# BlueTooth.net
KiCad netlist of a schematic drawn in Altium Designer
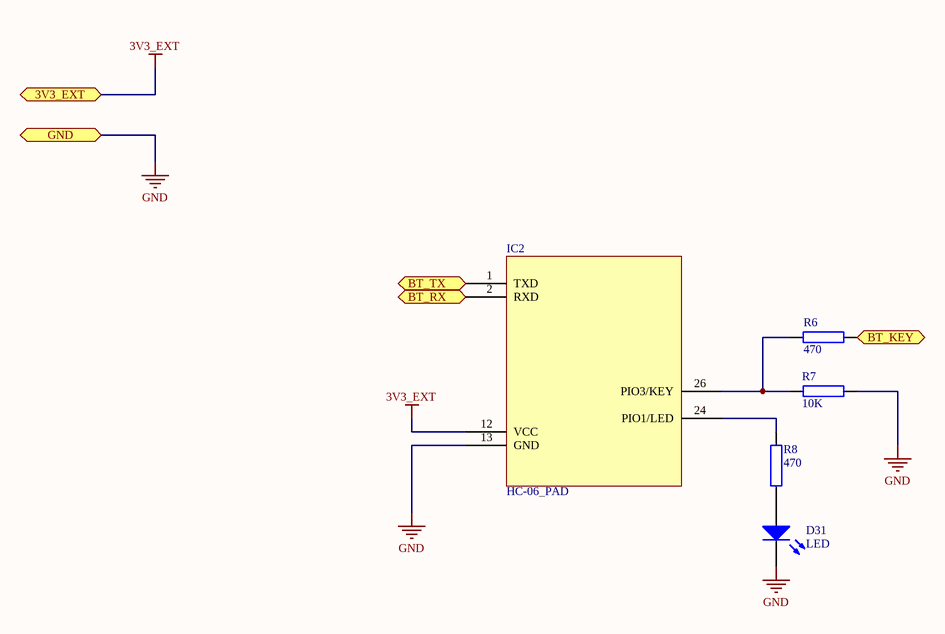
[diagram p0: BlueTooth.SchDoc]

(export (version "E")
  (design (tool "Eeschema 10.0.6"))
  (components
    (comp (ref "D31")
      (value "LED")
      (footprint "LED_0603")
      (description "Typical INFRARED GaAs LED")
      (fields (field (name "PUBLISHER") "Altium Limited"))
      (libsource (lib "Quadcopter") (part "LED"))
    )
    (comp (ref "IC2")
      (value "HC-06_PAD")
      (footprint "HC-0X_PAD")
      (libsource (lib "Quadcopter") (part "HC-06_PAD"))
    )
    (comp (ref "R6")
      (value "470")
      (footprint "R0603")
      (description "Resistor")
      (fields (field (name "PUBLISHER") "Altium Limited"))
      (libsource (lib "Quadcopter") (part "Res3"))
    )
    (comp (ref "R7")
      (value "10K")
      (footprint "R0603")
      (description "Resistor")
      (fields (field (name "PUBLISHER") "Altium Limited"))
      (libsource (lib "Quadcopter") (part "Res3"))
    )
    (comp (ref "R8")
      (value "470")
      (footprint "R0603")
      (description "Resistor")
      (fields (field (name "PUBLISHER") "Altium Limited"))
      (libsource (lib "Quadcopter") (part "Res3"))
    )
  )
  (nets
    (net (code "1") (name "/BT_KEY") (class "Default")
      (node (ref "R6") (pin "2") (pinfunction "2_2") (pintype "passive"))
    )
    (net (code "2") (name "/BT_RX") (class "Default")
      (node (ref "IC2") (pin "2") (pinfunction "RXD_2") (pintype "passive"))
    )
    (net (code "3") (name "/BT_TX") (class "Default")
      (node (ref "IC2") (pin "1") (pinfunction "TXD_1") (pintype "passive"))
    )
    (net (code "4") (name "3V3_EXT") (class "Default")
      (node (ref "IC2") (pin "12") (pinfunction "VCC_12") (pintype "passive"))
    )
    (net (code "5") (name "GND") (class "Default")
      (node (ref "D31") (pin "2") (pinfunction "K_2") (pintype "passive"))
      (node (ref "IC2") (pin "13") (pinfunction "GND_13") (pintype "passive"))
      (node (ref "R7") (pin "2") (pinfunction "2_2") (pintype "passive"))
    )
    (net (code "6") (name "Net-(D31-A)") (class "Default")
      (node (ref "D31") (pin "1") (pinfunction "A_1") (pintype "passive"))
      (node (ref "R8") (pin "1") (pinfunction "1_1") (pintype "passive"))
    )
    (net (code "7") (name "Net-(IC2-PIO1{slash}LED)") (class "Default")
      (node (ref "IC2") (pin "24") (pinfunction "PIO1/LED_24") (pintype "passive"))
      (node (ref "R8") (pin "2") (pinfunction "2_2") (pintype "passive"))
    )
    (net (code "8") (name "Net-(IC2-PIO3{slash}KEY)") (class "Default")
      (node (ref "IC2") (pin "26") (pinfunction "PIO3/KEY_26") (pintype "passive"))
      (node (ref "R6") (pin "1") (pinfunction "1_1") (pintype "passive"))
      (node (ref "R7") (pin "1") (pinfunction "1_1") (pintype "passive"))
    )
  )
)
